# InterfaceDataTelemetrie.net
KiCad netlist of a schematic drawn in Altium Designer
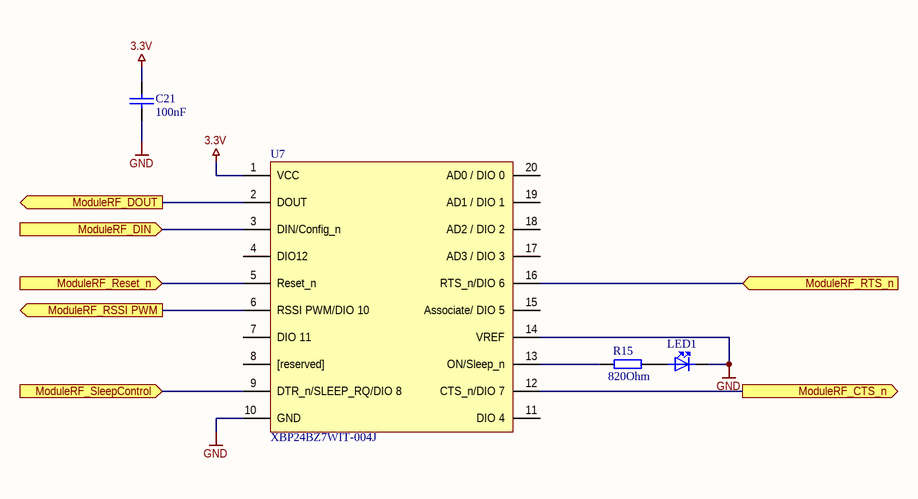
[diagram p0: InterfaceDataTelemetrie.SchDoc]

(export (version "E")
  (design (tool "Eeschema 10.0.6"))
  (components
    (comp (ref "C21")
      (value "100nF")
      (footprint "060301")
      (description "CAPA")
      (fields (field (name "Comment") "GRM188R71E104KA01D"))
      (libsource (lib "General-Sch-205") (part "CAPA"))
    )
    (comp (ref "LED1")
      (value "LG L29K-G2J1-24-Z")
      (footprint "060301_led")
      (libsource (lib "Schlib1") (part "LED"))
    )
    (comp (ref "R15")
      (value "820Ohm")
      (footprint "080501")
      (fields (field (name "Comment") "RMCF0805JT820R"))
      (libsource (lib "General-Sch-205") (part "RES"))
    )
    (comp (ref "U7")
      (value "XBP24BZ7WIT-004J")
      (footprint "XBee-Pro")
      (libsource (lib "Schlib1") (part "MaxStream XBee-PRO"))
    )
  )
  (nets
    (net (code "1") (name "/ModuleRF_CTS_n") (class "Default")
      (node (ref "U7") (pin "12") (pinfunction "CTS_n/DIO_7_12") (pintype "passive"))
    )
    (net (code "2") (name "/ModuleRF_DIN") (class "Default")
      (node (ref "U7") (pin "3") (pinfunction "DIN/Config_n_3") (pintype "passive"))
    )
    (net (code "3") (name "/ModuleRF_DOUT") (class "Default")
      (node (ref "U7") (pin "2") (pinfunction "DOUT_2") (pintype "passive"))
    )
    (net (code "4") (name "/ModuleRF_RSSI PWM") (class "Default")
      (node (ref "U7") (pin "6") (pinfunction "RSSI_PWM/DIO_10_6") (pintype "passive"))
    )
    (net (code "5") (name "/ModuleRF_RTS_n") (class "Default")
      (node (ref "U7") (pin "16") (pinfunction "RTS_n/DIO_6_16") (pintype "passive"))
    )
    (net (code "6") (name "/ModuleRF_Reset_n") (class "Default")
      (node (ref "U7") (pin "5") (pinfunction "Reset_n_5") (pintype "passive"))
    )
    (net (code "7") (name "/ModuleRF_SleepControl") (class "Default")
      (node (ref "U7") (pin "9") (pinfunction "DTR_n/SLEEP_RQ/DIO_8_9") (pintype "passive"))
    )
    (net (code "8") (name "3.3V") (class "Default")
      (node (ref "C21") (pin "1") (pintype "passive"))
      (node (ref "U7") (pin "1") (pinfunction "VCC_1") (pintype "passive"))
    )
    (net (code "9") (name "GND") (class "Default")
      (node (ref "C21") (pin "2") (pintype "passive"))
      (node (ref "LED1") (pin "2") (pinfunction "CATHODE_2") (pintype "passive"))
      (node (ref "U7") (pin "10") (pinfunction "GND_10") (pintype "passive"))
      (node (ref "U7") (pin "14") (pinfunction "VREF_14") (pintype "passive"))
    )
    (net (code "10") (name "Net-(LED1-ANODE)") (class "Default")
      (node (ref "LED1") (pin "1") (pinfunction "ANODE_1") (pintype "passive"))
      (node (ref "R15") (pin "2") (pintype "passive"))
    )
    (net (code "11") (name "Net-(U7-ON{slash}Sleep_n)") (class "Default")
      (node (ref "R15") (pin "1") (pintype "passive"))
      (node (ref "U7") (pin "13") (pinfunction "ON/Sleep_n_13") (pintype "passive"))
    )
    (net (code "12") (name "unconnected-(U7-AD0_{slash}_DIO_0-Pad20)") (class "Default")
      (node (ref "U7") (pin "20") (pinfunction "AD0_/_DIO_0_20") (pintype "passive"))
    )
    (net (code "13") (name "unconnected-(U7-AD1_{slash}_DIO_1-Pad19)") (class "Default")
      (node (ref "U7") (pin "19") (pinfunction "AD1_/_DIO_1_19") (pintype "passive"))
    )
    (net (code "14") (name "unconnected-(U7-AD2_{slash}_DIO_2-Pad18)") (class "Default")
      (node (ref "U7") (pin "18") (pinfunction "AD2_/_DIO_2_18") (pintype "passive"))
    )
    (net (code "15") (name "unconnected-(U7-AD3_{slash}_DIO_3-Pad17)") (class "Default")
      (node (ref "U7") (pin "17") (pinfunction "AD3_/_DIO_3_17") (pintype "passive"))
    )
    (net (code "16") (name "unconnected-(U7-Associate{slash}_DIO_5-Pad15)") (class "Default")
      (node (ref "U7") (pin "15") (pinfunction "Associate/_DIO_5_15") (pintype "passive"))
    )
    (net (code "17") (name "unconnected-(U7-DIO12-Pad4)") (class "Default")
      (node (ref "U7") (pin "4") (pinfunction "DIO12_4") (pintype "passive"))
    )
    (net (code "18") (name "unconnected-(U7-DIO_4-Pad11)") (class "Default")
      (node (ref "U7") (pin "11") (pinfunction "DIO_4_11") (pintype "passive"))
    )
    (net (code "19") (name "unconnected-(U7-DIO_11-Pad7)") (class "Default")
      (node (ref "U7") (pin "7") (pinfunction "DIO_11_7") (pintype "passive"))
    )
    (net (code "20") (name "unconnected-(U7-[reserved]-Pad8)") (class "Default")
      (node (ref "U7") (pin "8") (pinfunction "[reserved]_8") (pintype "passive"))
    )
  )
)
